# CCjammerRev1_TOP.net
KiCad netlist of a schematic drawn in Altium Designer
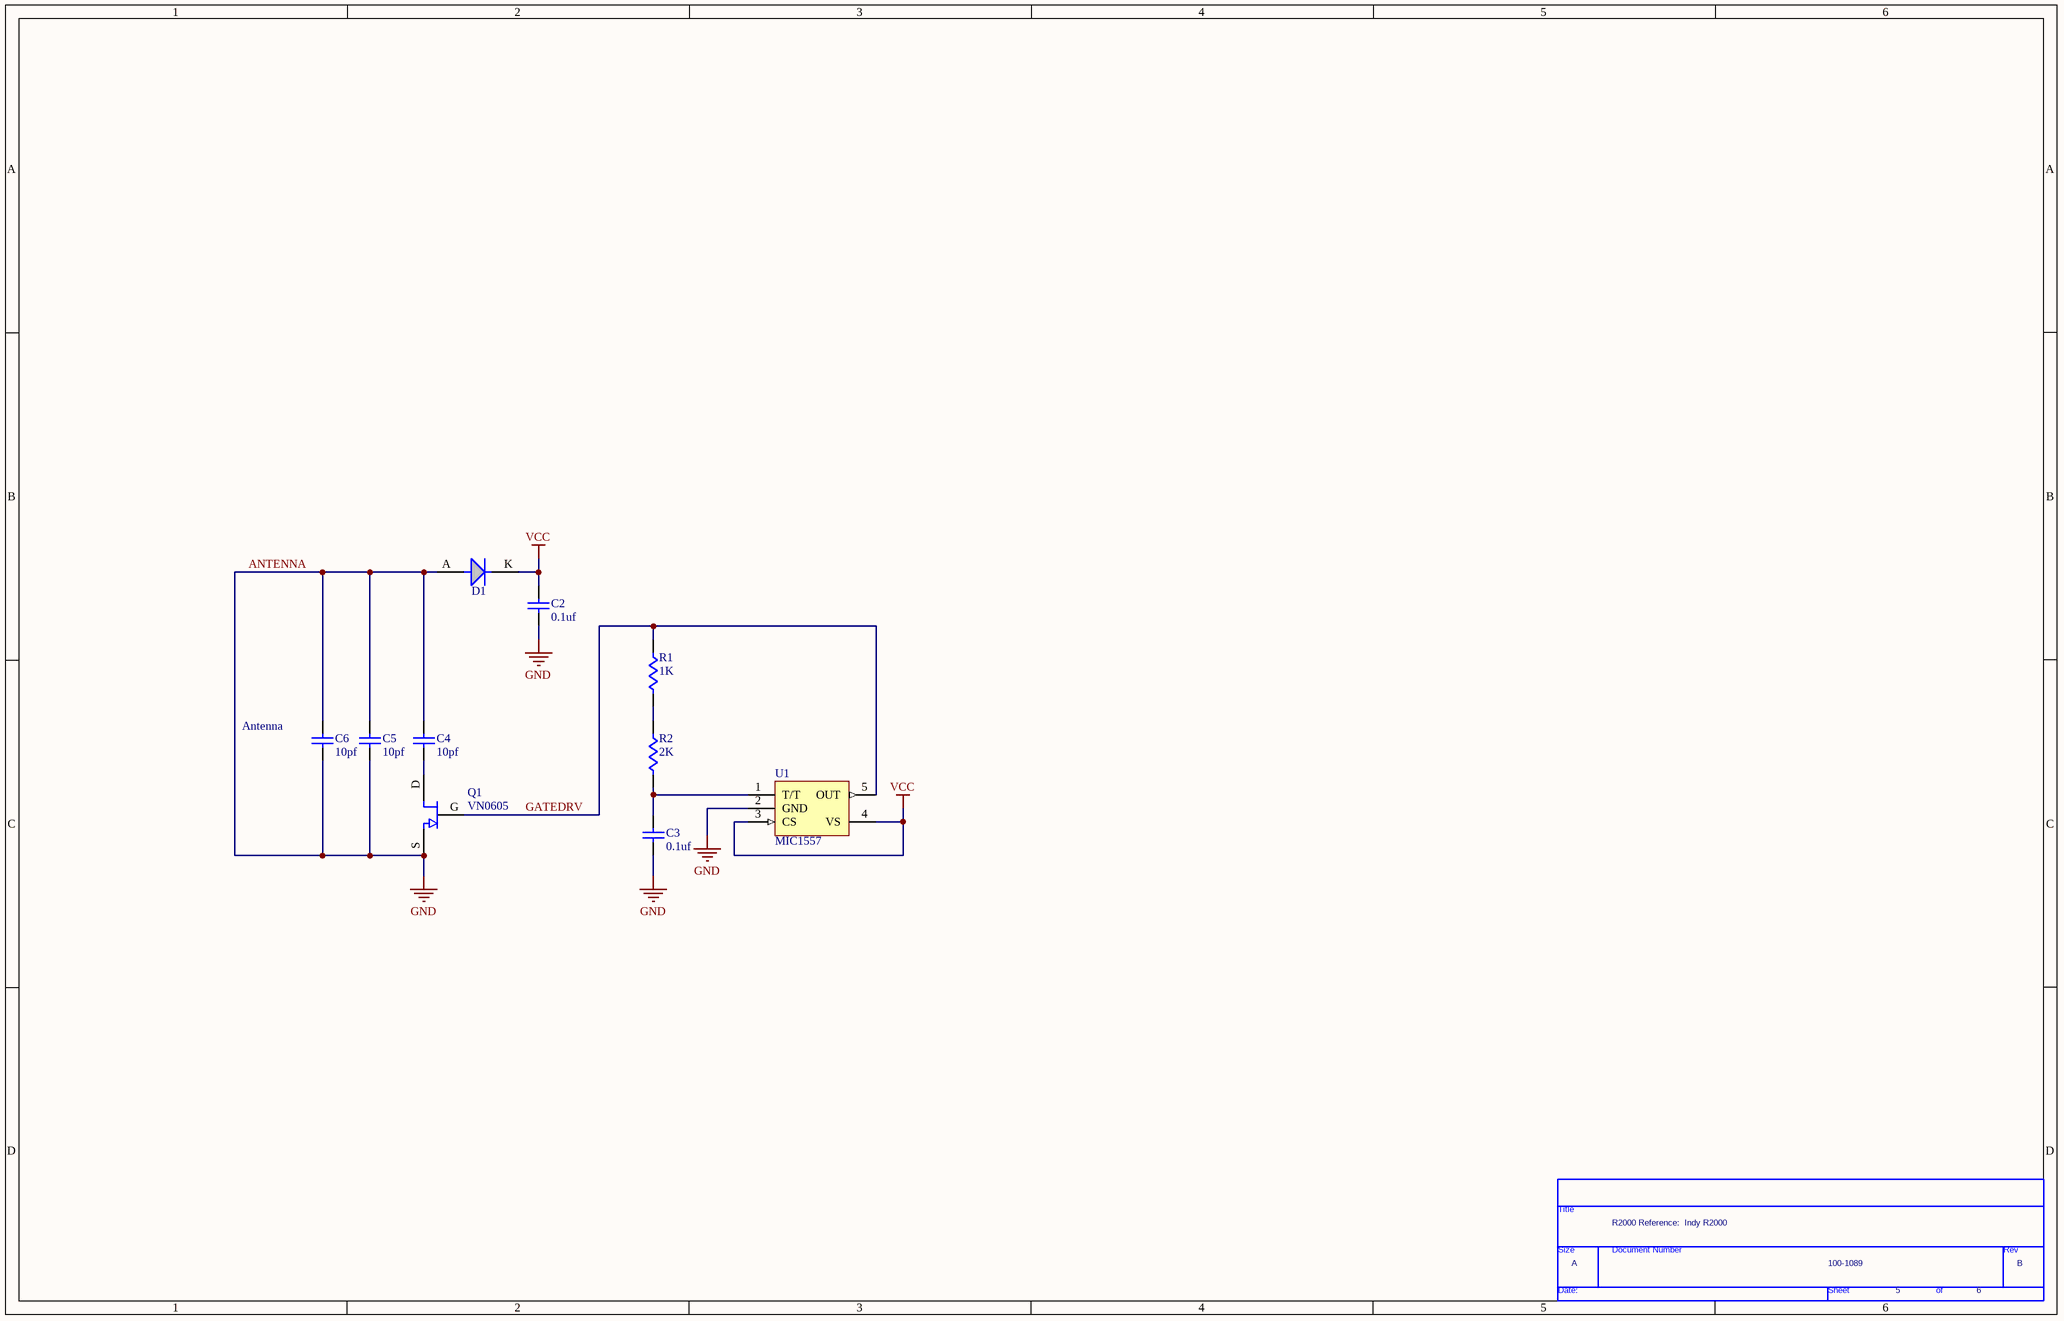
[diagram p0: CCjammerRev1_TOP.SchDoc]

(export (version "E")
  (design (tool "Eeschema 10.0.6"))
  (components
    (comp (ref "*")
      (value "TitleBlock0")
      (fields
        (field (name "PAGE COUNT") "6")
        (field (name "PAGE NUMBER") "5")
        (field (name "PAGE SIZE") "A")
        (field (name "TITLE") "R2000 Reference:  Indy R2000")
        (field (name "REVCODE") "B")
        (field (name "DOC") "100-1089")
      )
      (libsource (lib "*") (part "TitleBlock0"))
    )
    (comp (ref "C2")
      (value "0.1uf")
      (footprint "0603_072205")
      (description "Capacitor")
      (fields (field (name "PARTNO") "TMK212BJ475KG-T"))
      (libsource (lib "Miscellaneous Devices") (part "Cap"))
    )
    (comp (ref "C3")
      (value "0.1uf")
      (footprint "0603_072205")
      (description "Capacitor")
      (libsource (lib "Miscellaneous Devices") (part "Cap"))
    )
    (comp (ref "C4")
      (value "10pf")
      (footprint "0603_072205")
      (description "Capacitor")
      (libsource (lib "Miscellaneous Devices") (part "Cap"))
    )
    (comp (ref "C5")
      (value "10pf")
      (footprint "0603_072205")
      (description "Capacitor")
      (libsource (lib "Miscellaneous Devices") (part "Cap"))
    )
    (comp (ref "C6")
      (value "10pf")
      (footprint "0603_072205")
      (description "Capacitor")
      (libsource (lib "Miscellaneous Devices") (part "Cap"))
    )
    (comp (ref "D1")
      (value "DIODE")
      (footprint "SOD323_072005")
      (fields (field (name "PARTNO") "568-6022-2-ND") (field (name "MFG") "NXP SEMICONDUCTOR"))
      (libsource (lib "Common") (part "DIODE"))
    )
    (comp (ref "Q1")
      (value "VN0605")
      (footprint "SOT23 FET_012005")
      (fields (field (name "PARTNO") "VN0605T") (field (name "MFG") "Vishay"))
      (libsource (lib "Common") (part "FET N CHANNEL"))
    )
    (comp (ref "R1")
      (value "1K")
      (footprint "0603_072205")
      (fields (field (name "PARTNO") "RES-0000"))
      (libsource (lib "Discrete") (part "RESISTOR"))
    )
    (comp (ref "R2")
      (value "2K")
      (footprint "0603_072205")
      (fields (field (name "PARTNO") "RES-0000"))
      (libsource (lib "Discrete") (part "RESISTOR"))
    )
    (comp (ref "U1")
      (value "MIC1557")
      (footprint "SOT25_030205")
      (fields (field (name "MFG") "Micrel") (field (name "PARTNO") "MIC1557YM5"))
      (libsource (lib "Common") (part "MIC1555"))
    )
  )
  (nets
    (net (code "1") (name "/GATEDRV") (class "Default")
      (node (ref "Q1") (pin "G") (pinfunction "G_G") (pintype "passive"))
      (node (ref "R1") (pin "2") (pinfunction "2_2") (pintype "passive"))
      (node (ref "U1") (pin "5") (pinfunction "OUT_5") (pintype "output"))
    )
    (net (code "2") (name "GND") (class "Default")
      (node (ref "C2") (pin "1") (pinfunction "1_1") (pintype "passive"))
      (node (ref "C3") (pin "1") (pinfunction "1_1") (pintype "passive"))
      (node (ref "C4") (pin "2") (pinfunction "2_2") (pintype "passive"))
      (node (ref "C5") (pin "1") (pinfunction "1_1") (pintype "passive"))
      (node (ref "C5") (pin "2") (pinfunction "2_2") (pintype "passive"))
      (node (ref "C6") (pin "1") (pinfunction "1_1") (pintype "passive"))
      (node (ref "C6") (pin "2") (pinfunction "2_2") (pintype "passive"))
      (node (ref "D1") (pin "A") (pinfunction "A_A") (pintype "passive"))
      (node (ref "Q1") (pin "S") (pinfunction "S_S") (pintype "passive"))
      (node (ref "U1") (pin "2") (pinfunction "GND_2") (pintype "power_in"))
    )
    (net (code "3") (name "Net-(C4-Pad1)") (class "Default")
      (node (ref "C4") (pin "1") (pinfunction "1_1") (pintype "passive"))
      (node (ref "Q1") (pin "D") (pinfunction "D_D") (pintype "passive"))
    )
    (net (code "4") (name "Net-(R1-Pad1)") (class "Default")
      (node (ref "R1") (pin "1") (pinfunction "1_1") (pintype "passive"))
      (node (ref "R2") (pin "2") (pinfunction "2_2") (pintype "passive"))
    )
    (net (code "5") (name "Net-(U1-T{slash}T)") (class "Default")
      (node (ref "C3") (pin "2") (pinfunction "2_2") (pintype "passive"))
      (node (ref "R2") (pin "1") (pinfunction "1_1") (pintype "passive"))
      (node (ref "U1") (pin "1") (pinfunction "T/T_1") (pintype "passive"))
    )
    (net (code "6") (name "VCC") (class "Default")
      (node (ref "C2") (pin "2") (pinfunction "2_2") (pintype "passive"))
      (node (ref "D1") (pin "K") (pinfunction "K_K") (pintype "passive"))
      (node (ref "U1") (pin "3") (pinfunction "CS_3") (pintype "input"))
      (node (ref "U1") (pin "4") (pinfunction "VS_4") (pintype "power_in"))
    )
  )
)
